# 10_Motor_Driver_2.net
KiCad netlist of a schematic drawn in Altium Designer
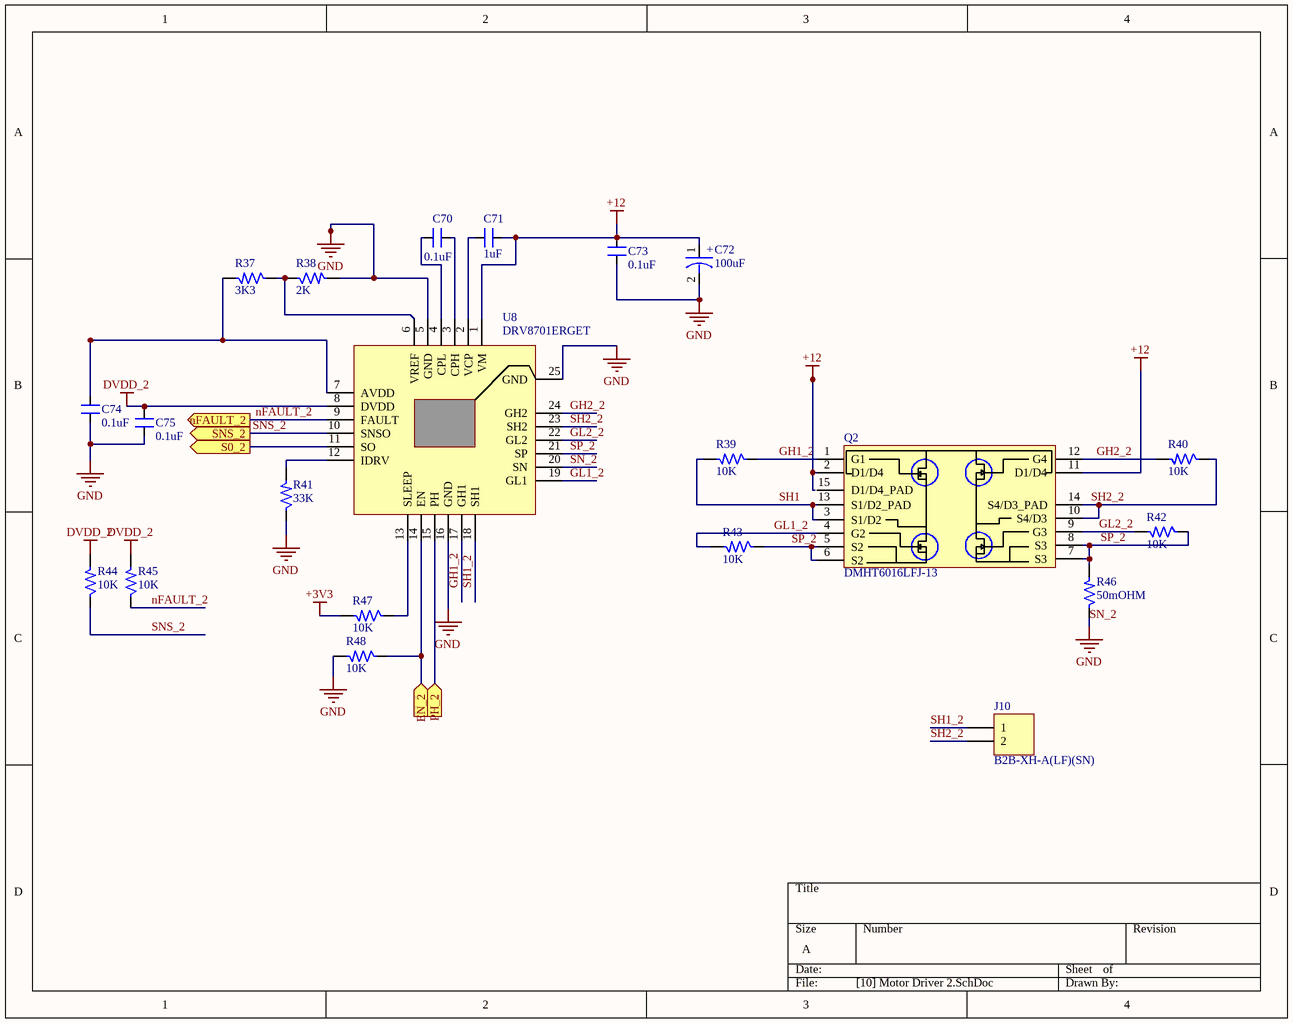
[diagram p0: [10] Motor Driver 2.SchDoc]

(export (version "E")
  (design (tool "Eeschema 10.0.6"))
  (components
    (comp (ref "C70")
      (value "0.1uF")
      (footprint "CAP_0805")
      (description "0.1µF ±10% 50V Ceramic Capacitor X7R 0805 (2012 Metric)")
      (fields
        (field (name "MANUFACTURER") "Samsung")
        (field (name "MANUFACTURER PART NUMBER") "CL21B104KBCNNNC")
      )
      (libsource (lib "ESTEEMPCBLIB") (part "CAP_0.1uF-50V-10%-0805"))
    )
    (comp (ref "C71")
      (value "1uF")
      (footprint "CAP_0805")
      (description "1µF ±5% 50V Ceramic Capacitor X7R 0805 (2012 Metric)")
      (fields
        (field (name "MANUFACTURER") "Samsung")
        (field (name "MANUFACTURER PART NUMBER") "CC0805JKX7R9BB105")
      )
      (libsource (lib "ESTEEMPCBLIB") (part "CAP_1uF-50V-5%-0805"))
    )
    (comp (ref "C72")
      (value "100uF")
      (footprint "ACAP_P236_D305_H303_RAD")
      (description "100µF 25V Aluminum Electrolytic Capacitors Radial, Can - SMD 1000 Hrs @ 105°C")
      (fields
        (field (name "MANUFACTURER") "Nichicon")
        (field (name "MANUFACTURER PART NUMBER") "UWT1E101MCL1GS")
      )
      (libsource (lib "ESTEEMPCBLIB") (part "CAP-P_100uF-25V-20%-RAD"))
    )
    (comp (ref "C73")
      (value "0.1uF")
      (footprint "CAP_0805")
      (description "0.1µF ±10% 50V Ceramic Capacitor X7R 0805 (2012 Metric)")
      (fields
        (field (name "MANUFACTURER") "Samsung")
        (field (name "MANUFACTURER PART NUMBER") "CL21B104KBCNNNC")
      )
      (libsource (lib "ESTEEMPCBLIB") (part "CAP_0.1uF-50V-10%-0805"))
    )
    (comp (ref "C74")
      (value "0.1uF")
      (footprint "CAP_0805")
      (description "0.1µF ±5% 50V Ceramic Capacitor X7R 0805 (2012 Metric)")
      (fields
        (field (name "MANUFACTURER") "AVX Corporation")
        (field (name "MANUFACTURER PART NUMBER") "08055C104JAT4A")
      )
      (libsource (lib "ESTEEMPCBLIB") (part "CAP_0.1uF-50V-5%-0805"))
    )
    (comp (ref "C75")
      (value "0.1uF")
      (footprint "CAP_0805")
      (description "0.1µF ±5% 50V Ceramic Capacitor X7R 0805 (2012 Metric)")
      (fields
        (field (name "MANUFACTURER") "AVX Corporation")
        (field (name "MANUFACTURER PART NUMBER") "08055C104JAT4A")
      )
      (libsource (lib "ESTEEMPCBLIB") (part "CAP_0.1uF-50V-5%-0805"))
    )
    (comp (ref "J10")
      (value "B2B-XH-A(LF)(SN)")
      (footprint "CON2_100_B2B-XH-A_TH_ST")
      (description "2 Pins, 1 Row 2.54mm Pitch, Straight Connector, male")
      (fields (field (name "MANUFACTURER") "JST") (field (name "MATING PART NUMBER") "XHP-2"))
      (libsource (lib "ESTEEMPCBLIB") (part "CON-PLG_2X1-100-ST-TH"))
    )
    (comp (ref "Q2")
      (value "DMHT6016LFJ-13")
      (footprint "DFN5045-12_33_212_27X15_SMD_1")
      (description "Mosfet Array 4 N-Channel 14.8A (Ta) Surface Mount V-DFN5045-12")
      (fields (field (name "MANUFACTURER") "ON Semiconductor"))
      (libsource (lib "ESTEEMPCBLIB") (part "MOSFET-N_60V-14.8A-V-DFN5045-12"))
    )
    (comp (ref "R37")
      (value "3K3")
      (footprint "RES_0603")
      (description "3.3 kOhms ±1% 0.1W, 1/10W Chip Resistor 0603 (1608 Metric) Automotive AEC-Q200 Thick Film")
      (fields (field (name "MANUFACTURER") "Wilson") (field (name "MANUFACTURER PART NUMBER") "WR06X3301FTL"))
      (libsource (lib "ESTEEMPCBLIB") (part "RES_3.3K-0.1W-1%-0603"))
    )
    (comp (ref "R38")
      (value "2K")
      (footprint "RES_0603")
      (fields
        (field (name "MANUFACTURER") "Stackpole Electronics")
        (field (name "MANUFACTURER PART NUMBER") "RNCP0603FTD2K00")
      )
      (libsource (lib "ESTEEMPCBLIB") (part "RES_2K-0.125W-1%-0603"))
    )
    (comp (ref "R39")
      (value "10K")
      (footprint "RES_0603")
      (description "10 kOhms ±1% 0.1W, 1/10W Chip Resistor 0603 (1608 Metric) Automotive AEC-Q200 Thick Film")
      (fields (field (name "MANUFACTURER") "Walsin") (field (name "MANUFACTURER PART NUMBER") "WR06X1002FTL"))
      (libsource (lib "ESTEEMPCBLIB") (part "RES_10K-0.1W-1%-0603"))
    )
    (comp (ref "R40")
      (value "10K")
      (footprint "RES_0603")
      (description "10 kOhms ±1% 0.1W, 1/10W Chip Resistor 0603 (1608 Metric) Automotive AEC-Q200 Thick Film")
      (fields (field (name "MANUFACTURER") "Walsin") (field (name "MANUFACTURER PART NUMBER") "WR06X1002FTL"))
      (libsource (lib "ESTEEMPCBLIB") (part "RES_10K-0.1W-1%-0603"))
    )
    (comp (ref "R41")
      (value "33K")
      (footprint "RES_0805")
      (fields
        (field (name "MANUFACTURER") "Vishay BCcomponents")
        (field (name "MANUFACTURER PART NUMBER") "CRG0805F33K")
      )
      (libsource (lib "ESTEEMPCBLIB") (part "RES_33K-0.125W-1%-0805"))
    )
    (comp (ref "R42")
      (value "10K")
      (footprint "RES_0603")
      (description "10 kOhms ±1% 0.1W, 1/10W Chip Resistor 0603 (1608 Metric) Automotive AEC-Q200 Thick Film")
      (fields (field (name "MANUFACTURER") "Walsin") (field (name "MANUFACTURER PART NUMBER") "WR06X1002FTL"))
      (libsource (lib "ESTEEMPCBLIB") (part "RES_10K-0.1W-1%-0603"))
    )
    (comp (ref "R43")
      (value "10K")
      (footprint "RES_0603")
      (description "10 kOhms ±1% 0.1W, 1/10W Chip Resistor 0603 (1608 Metric) Automotive AEC-Q200 Thick Film")
      (fields (field (name "MANUFACTURER") "Walsin") (field (name "MANUFACTURER PART NUMBER") "WR06X1002FTL"))
      (libsource (lib "ESTEEMPCBLIB") (part "RES_10K-0.1W-1%-0603"))
    )
    (comp (ref "R44")
      (value "10K")
      (footprint "RES_0603")
      (description "10 kOhms ±1% 0.1W, 1/10W Chip Resistor 0603 (1608 Metric) Automotive AEC-Q200 Thick Film")
      (fields (field (name "MANUFACTURER") "Walsin") (field (name "MANUFACTURER PART NUMBER") "WR06X1002FTL"))
      (libsource (lib "ESTEEMPCBLIB") (part "RES_10K-0.1W-1%-0603"))
    )
    (comp (ref "R45")
      (value "10K")
      (footprint "RES_0603")
      (description "10 kOhms ±1% 0.1W, 1/10W Chip Resistor 0603 (1608 Metric) Automotive AEC-Q200 Thick Film")
      (fields (field (name "MANUFACTURER") "Walsin") (field (name "MANUFACTURER PART NUMBER") "WR06X1002FTL"))
      (libsource (lib "ESTEEMPCBLIB") (part "RES_10K-0.1W-1%-0603"))
    )
    (comp (ref "R46")
      (value "50mOHM")
      (footprint "RES_2512")
      (fields
        (field (name "MANUFACTURER") "Yageo")
        (field (name "MANUFACTURER PART NUMBER") "PA2512FKF7W0R05E")
      )
      (libsource (lib "ESTEEMPCBLIB") (part "RES_50mOhm-2W-1%-2512"))
    )
    (comp (ref "R47")
      (value "10K")
      (footprint "RES_0603")
      (description "10 kOhms ±1% 0.1W, 1/10W Chip Resistor 0603 (1608 Metric) Automotive AEC-Q200 Thick Film")
      (fields (field (name "MANUFACTURER") "Walsin") (field (name "MANUFACTURER PART NUMBER") "WR06X1002FTL"))
      (libsource (lib "ESTEEMPCBLIB") (part "RES_10K-0.1W-1%-0603"))
    )
    (comp (ref "R48")
      (value "10K")
      (footprint "RES_0603")
      (description "10 kOhms ±1% 0.1W, 1/10W Chip Resistor 0603 (1608 Metric) Automotive AEC-Q200 Thick Film")
      (fields (field (name "MANUFACTURER") "Walsin") (field (name "MANUFACTURER PART NUMBER") "WR06X1002FTL"))
      (libsource (lib "ESTEEMPCBLIB") (part "RES_10K-0.1W-1%-0603"))
    )
    (comp (ref "U8")
      (value "DRV8701ERGET")
      (footprint "VFQFN24_19.6_196_12X32_SMD_1")
      (description "Motor Driver Power MOSFET Parallel 24-VQFN (4x4)")
      (fields (field (name "MANUFACTURER") "Texas Instruments"))
      (libsource (lib "ESTEEMPCBLIB") (part "IC_DRV8701ERGET"))
    )
  )
  (nets
    (net (code "1") (name "+3V3") (class "Default")
      (node (ref "R47") (pin "2") (pinfunction "2_2") (pintype "passive"))
    )
    (net (code "2") (name "+12") (class "Default")
      (node (ref "C71") (pin "2") (pinfunction "2_2") (pintype "passive"))
      (node (ref "C72") (pin "1") (pinfunction "1_1") (pintype "passive"))
      (node (ref "C73") (pin "2") (pinfunction "2_2") (pintype "passive"))
      (node (ref "Q2") (pin "11") (pinfunction "D1/D4_11") (pintype "passive"))
      (node (ref "Q2") (pin "2") (pinfunction "D1/D4_2") (pintype "passive"))
      (node (ref "U8") (pin "1") (pinfunction "VM_1") (pintype "passive"))
    )
    (net (code "3") (name "/EN_2") (class "Default")
      (node (ref "R48") (pin "1") (pinfunction "1_1") (pintype "passive"))
      (node (ref "U8") (pin "14") (pinfunction "EN_14") (pintype "passive"))
    )
    (net (code "4") (name "/GH1_2") (class "Default")
      (node (ref "Q2") (pin "1") (pinfunction "G1_1") (pintype "passive"))
      (node (ref "R39") (pin "1") (pinfunction "1_1") (pintype "passive"))
      (node (ref "U8") (pin "17") (pinfunction "GH1_17") (pintype "passive"))
    )
    (net (code "5") (name "/GH2_2") (class "Default")
      (node (ref "Q2") (pin "12") (pinfunction "G4_12") (pintype "passive"))
      (node (ref "R40") (pin "2") (pinfunction "2_2") (pintype "passive"))
      (node (ref "U8") (pin "24") (pinfunction "GH2_24") (pintype "passive"))
    )
    (net (code "6") (name "/GL1_2") (class "Default")
      (node (ref "Q2") (pin "4") (pinfunction "G2_4") (pintype "passive"))
      (node (ref "R43") (pin "2") (pinfunction "2_2") (pintype "passive"))
      (node (ref "U8") (pin "19") (pinfunction "GL1_19") (pintype "passive"))
    )
    (net (code "7") (name "/GL2_2") (class "Default")
      (node (ref "Q2") (pin "9") (pinfunction "G3_9") (pintype "passive"))
      (node (ref "R42") (pin "2") (pinfunction "2_2") (pintype "passive"))
      (node (ref "U8") (pin "22") (pinfunction "GL2_22") (pintype "passive"))
    )
    (net (code "8") (name "/PH_2") (class "Default")
      (node (ref "U8") (pin "15") (pinfunction "PH_15") (pintype "passive"))
    )
    (net (code "9") (name "/S0_2") (class "Default")
      (node (ref "U8") (pin "11") (pinfunction "SO_11") (pintype "passive"))
    )
    (net (code "10") (name "/SH1") (class "Default")
      (node (ref "Q2") (pin "13") (pinfunction "S1/D2_PAD_13") (pintype "passive"))
      (node (ref "Q2") (pin "3") (pinfunction "S1/D2_3") (pintype "passive"))
      (node (ref "R39") (pin "2") (pinfunction "2_2") (pintype "passive"))
    )
    (net (code "11") (name "/SH1_2") (class "Default")
      (node (ref "J10") (pin "1") (pinfunction "1_1") (pintype "passive"))
      (node (ref "U8") (pin "18") (pinfunction "SH1_18") (pintype "passive"))
    )
    (net (code "12") (name "/SH2_2") (class "Default")
      (node (ref "J10") (pin "2") (pinfunction "2_2") (pintype "passive"))
      (node (ref "Q2") (pin "10") (pinfunction "S4/D3_10") (pintype "passive"))
      (node (ref "Q2") (pin "14") (pinfunction "S4/D3_PAD_14") (pintype "passive"))
      (node (ref "R40") (pin "1") (pinfunction "1_1") (pintype "passive"))
      (node (ref "U8") (pin "23") (pinfunction "SH2_23") (pintype "passive"))
    )
    (net (code "13") (name "/SNS_2") (class "Default")
      (node (ref "R44") (pin "1") (pinfunction "1_1") (pintype "passive"))
      (node (ref "U8") (pin "10") (pinfunction "SNSO_10") (pintype "passive"))
    )
    (net (code "14") (name "/SP_2") (class "Default")
      (node (ref "Q2") (pin "5") (pinfunction "S2_5") (pintype "passive"))
      (node (ref "Q2") (pin "6") (pinfunction "S2_6") (pintype "passive"))
      (node (ref "Q2") (pin "7") (pinfunction "S3_7") (pintype "passive"))
      (node (ref "Q2") (pin "8") (pinfunction "S3_8") (pintype "passive"))
      (node (ref "R42") (pin "1") (pinfunction "1_1") (pintype "passive"))
      (node (ref "R43") (pin "1") (pinfunction "1_1") (pintype "passive"))
      (node (ref "R46") (pin "2") (pinfunction "2_2") (pintype "passive"))
      (node (ref "U8") (pin "21") (pinfunction "SP_21") (pintype "passive"))
    )
    (net (code "15") (name "/nFAULT_2") (class "Default")
      (node (ref "R45") (pin "1") (pinfunction "1_1") (pintype "passive"))
      (node (ref "U8") (pin "9") (pinfunction "FAULT_9") (pintype "passive"))
    )
    (net (code "16") (name "DVDD_2") (class "Default")
      (node (ref "C75") (pin "2") (pinfunction "2_2") (pintype "passive"))
      (node (ref "R44") (pin "2") (pinfunction "2_2") (pintype "passive"))
      (node (ref "R45") (pin "2") (pinfunction "2_2") (pintype "passive"))
      (node (ref "U8") (pin "8") (pinfunction "DVDD_8") (pintype "passive"))
    )
    (net (code "17") (name "GND") (class "Default")
      (node (ref "C72") (pin "2") (pinfunction "2_2") (pintype "passive"))
      (node (ref "C73") (pin "1") (pinfunction "1_1") (pintype "passive"))
      (node (ref "C74") (pin "1") (pinfunction "1_1") (pintype "passive"))
      (node (ref "C75") (pin "1") (pinfunction "1_1") (pintype "passive"))
      (node (ref "R38") (pin "2") (pinfunction "2_2") (pintype "passive"))
      (node (ref "R41") (pin "1") (pinfunction "1_1") (pintype "passive"))
      (node (ref "R46") (pin "1") (pinfunction "1_1") (pintype "passive"))
      (node (ref "R48") (pin "2") (pinfunction "2_2") (pintype "passive"))
      (node (ref "U8") (pin "16") (pinfunction "GND_16") (pintype "passive"))
      (node (ref "U8") (pin "20") (pinfunction "SN_20") (pintype "passive"))
      (node (ref "U8") (pin "25") (pinfunction "GND_25") (pintype "passive"))
      (node (ref "U8") (pin "5") (pinfunction "GND_5") (pintype "passive"))
    )
    (net (code "18") (name "Net-(U8-AVDD)") (class "Default")
      (node (ref "C74") (pin "2") (pinfunction "2_2") (pintype "passive"))
      (node (ref "R37") (pin "2") (pinfunction "2_2") (pintype "passive"))
      (node (ref "U8") (pin "7") (pinfunction "AVDD_7") (pintype "passive"))
    )
    (net (code "19") (name "Net-(U8-CPH)") (class "Default")
      (node (ref "C70") (pin "1") (pinfunction "1_1") (pintype "passive"))
      (node (ref "U8") (pin "3") (pinfunction "CPH_3") (pintype "passive"))
    )
    (net (code "20") (name "Net-(U8-CPL)") (class "Default")
      (node (ref "C70") (pin "2") (pinfunction "2_2") (pintype "passive"))
      (node (ref "U8") (pin "4") (pinfunction "CPL_4") (pintype "passive"))
    )
    (net (code "21") (name "Net-(U8-IDRV)") (class "Default")
      (node (ref "R41") (pin "2") (pinfunction "2_2") (pintype "passive"))
      (node (ref "U8") (pin "12") (pinfunction "IDRV_12") (pintype "passive"))
    )
    (net (code "22") (name "Net-(U8-SLEEP)") (class "Default")
      (node (ref "R47") (pin "1") (pinfunction "1_1") (pintype "passive"))
      (node (ref "U8") (pin "13") (pinfunction "SLEEP_13") (pintype "passive"))
    )
    (net (code "23") (name "Net-(U8-VCP)") (class "Default")
      (node (ref "C71") (pin "1") (pinfunction "1_1") (pintype "passive"))
      (node (ref "U8") (pin "2") (pinfunction "VCP_2") (pintype "passive"))
    )
    (net (code "24") (name "Net-(U8-VREF)") (class "Default")
      (node (ref "R37") (pin "1") (pinfunction "1_1") (pintype "passive"))
      (node (ref "R38") (pin "1") (pinfunction "1_1") (pintype "passive"))
      (node (ref "U8") (pin "6") (pinfunction "VREF_6") (pintype "passive"))
    )
    (net (code "25") (name "unconnected-(Q2-D1{slash}D4_PAD-Pad15)") (class "Default")
      (node (ref "Q2") (pin "15") (pinfunction "D1/D4_PAD_15") (pintype "passive"))
    )
  )
)
